# LEDController.net
KiCad netlist of a schematic drawn in Altium Designer
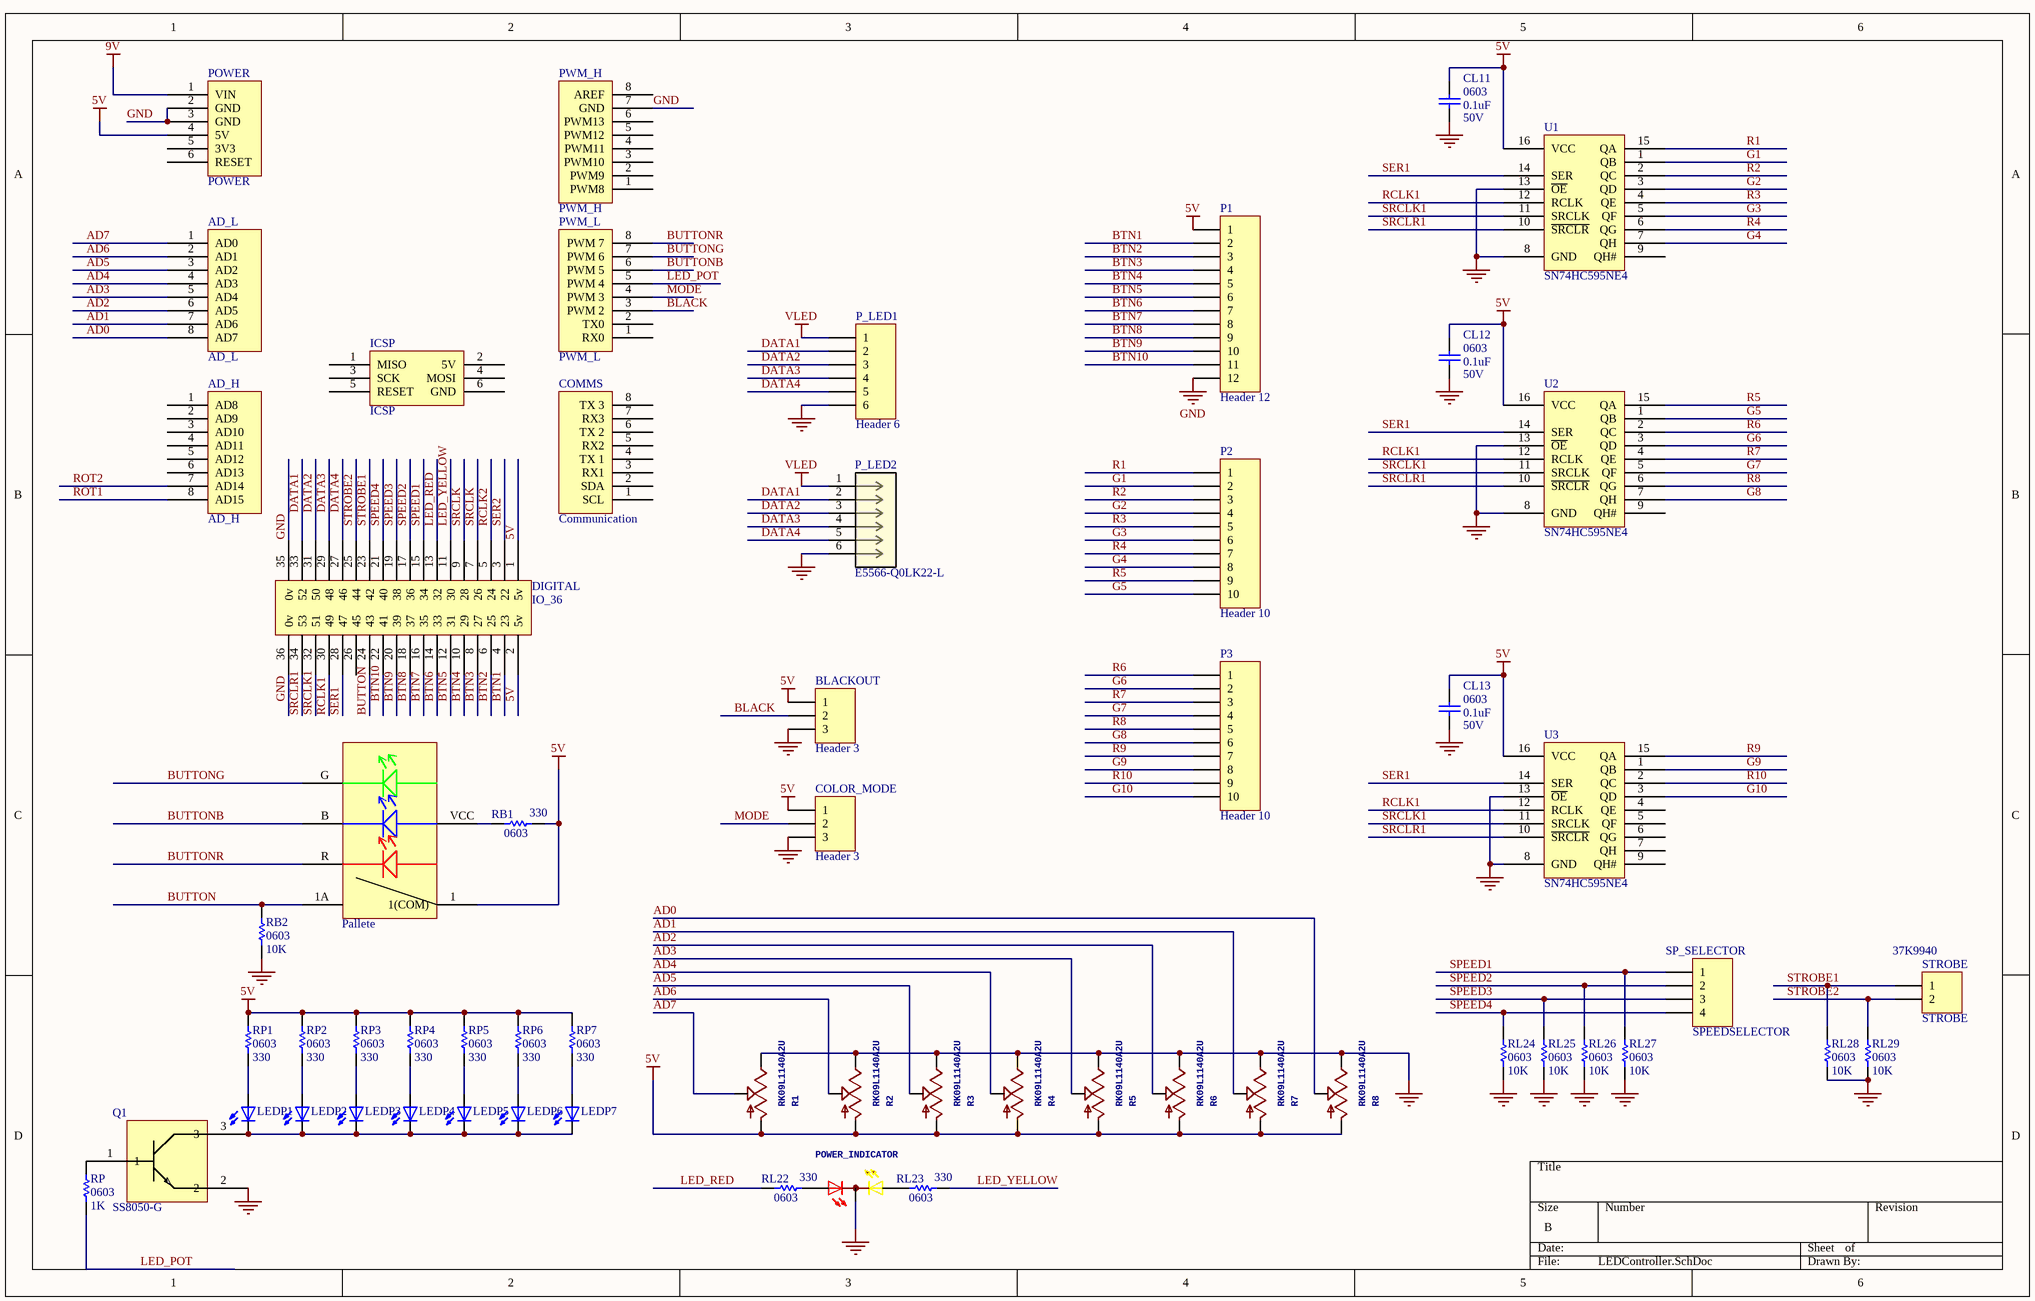
[diagram p0: LEDController.SchDoc]

(export (version "E")
  (design (tool "Eeschema 10.0.6"))
  (components
    (comp (ref "AD_H")
      (value "AD_H")
      (footprint "Header 8x1 8.5mm")
      (description "CONN HEADER VERT 8POS 2.54MM")
      (libsource (lib "Schlib") (part "AD_H"))
    )
    (comp (ref "AD_L")
      (value "AD_L")
      (footprint "Header 8x1 8.5mm")
      (description "CONN HEADER VERT 8POS 2.54MM")
      (libsource (lib "Schlib") (part "AD_L"))
    )
    (comp (ref "BLACKOUT")
      (value "Header 3")
      (footprint "B3B-PH-K-S(LF)(SN)")
      (description "CONN HEADER VERT 3POS 2MM")
      (fields (field (name "PUBLISHER") "Altium Limited"))
      (libsource (lib "Miscellaneous Connectors") (part "Header 3"))
    )
    (comp (ref "CL11")
      (value "0603")
      (footprint "C0603")
      (description "CAP CER 0.1UF 50V X5R 0603")
      (fields
        (field (name "ALTIUM_VALUE") "0.1uF")
        (field (name "VOLTAGE RATING") "50V")
        (field (name "TOLERANCE") "10%")
      )
      (libsource (lib "Miscellaneous Devices") (part "Cap"))
    )
    (comp (ref "CL12")
      (value "0603")
      (footprint "C0603")
      (description "CAP CER 0.1UF 50V X5R 0603")
      (fields
        (field (name "ALTIUM_VALUE") "0.1uF")
        (field (name "VOLTAGE RATING") "50V")
        (field (name "TOLERANCE") "10%")
      )
      (libsource (lib "Miscellaneous Devices") (part "Cap"))
    )
    (comp (ref "CL13")
      (value "0603")
      (footprint "C0603")
      (description "CAP CER 0.1UF 50V X5R 0603")
      (fields
        (field (name "ALTIUM_VALUE") "0.1uF")
        (field (name "VOLTAGE RATING") "50V")
        (field (name "TOLERANCE") "10%")
      )
      (libsource (lib "Miscellaneous Devices") (part "Cap"))
    )
    (comp (ref "COLOR_MODE")
      (value "Header 3")
      (footprint "B3B-PH-K-S(LF)(SN)")
      (description "CONN HEADER VERT 3POS 2MM")
      (fields (field (name "PUBLISHER") "Altium Limited"))
      (libsource (lib "Miscellaneous Connectors") (part "Header 3"))
    )
    (comp (ref "COMMS")
      (value "Communication")
      (footprint "Header 8x1 8.5mm")
      (description "CONN HEADER VERT 8POS 2.54MM")
      (libsource (lib "Schlib") (part "Communication"))
    )
    (comp (ref "DIGITAL")
      (value "IO_36")
      (footprint "HEADER 36X 8MM")
      (description "CONN HEADER VERT 36POS 2.54MM")
      (libsource (lib "Schlib") (part "IO_36"))
    )
    (comp (ref "ICSP") (value "ICSP") (footprint "ICSP") (libsource (lib "Schlib") (part "ICSP")))
    (comp (ref "LEDP1")
      (value "150060AS75000")
      (footprint "LED-0603-Amber")
      (description "Amber 605nm LED Indication - Discrete 2V 0603 (1608 Metric)")
      (libsource (lib "Schlib") (part "150060AS75000"))
    )
    (comp (ref "LEDP2")
      (value "150060AS75000")
      (footprint "LED-0603-Amber")
      (description "Amber 605nm LED Indication - Discrete 2V 0603 (1608 Metric)")
      (libsource (lib "Schlib") (part "150060AS75000"))
    )
    (comp (ref "LEDP3")
      (value "150060AS75000")
      (footprint "LED-0603-Amber")
      (description "Amber 605nm LED Indication - Discrete 2V 0603 (1608 Metric)")
      (libsource (lib "Schlib") (part "150060AS75000"))
    )
    (comp (ref "LEDP4")
      (value "150060AS75000")
      (footprint "LED-0603-Amber")
      (description "Amber 605nm LED Indication - Discrete 2V 0603 (1608 Metric)")
      (libsource (lib "Schlib") (part "150060AS75000"))
    )
    (comp (ref "LEDP5")
      (value "150060AS75000")
      (footprint "LED-0603-Amber")
      (description "Amber 605nm LED Indication - Discrete 2V 0603 (1608 Metric)")
      (libsource (lib "Schlib") (part "150060AS75000"))
    )
    (comp (ref "LEDP6")
      (value "150060AS75000")
      (footprint "LED-0603-Amber")
      (description "Amber 605nm LED Indication - Discrete 2V 0603 (1608 Metric)")
      (libsource (lib "Schlib") (part "150060AS75000"))
    )
    (comp (ref "LEDP7")
      (value "150060AS75000")
      (footprint "LED-0603-Amber")
      (description "Amber 605nm LED Indication - Discrete 2V 0603 (1608 Metric)")
      (libsource (lib "Schlib") (part "150060AS75000"))
    )
    (comp (ref "P1")
      (value "Header 12")
      (footprint "12Pos Header")
      (description "CONN HEADER VERT 12POS 2.54MM")
      (libsource (lib "Miscellaneous Connectors") (part "Header 12"))
    )
    (comp (ref "P2")
      (value "Header 10")
      (footprint "10POS HEADER")
      (description "CONN HEADER VERT 10POS 2.54MM")
      (fields (field (name "PUBLISHER") "Altium Limited"))
      (libsource (lib "Miscellaneous Connectors") (part "Header 10"))
    )
    (comp (ref "P3")
      (value "Header 10")
      (footprint "10POS HEADER")
      (description "CONN HEADER VERT 10POS 2.54MM")
      (fields (field (name "PUBLISHER") "Altium Limited"))
      (libsource (lib "Miscellaneous Connectors") (part "Header 10"))
    )
    (comp (ref "Pallete")
      (value "KP0115ANBKG03RGB-2SJB")
      (footprint "KP0115ANBKG03RGB-2SJB")
      (description "Pushbutton Switch SPST-NO Standard, Illuminated Through Hole")
      (libsource (lib "Schlib") (part "KP0115ANBKG03RGB-2SJB"))
    )
    (comp (ref "POWER")
      (value "POWER")
      (footprint "Header 6x1 8.5mm")
      (description "CONN HEADER VERT 6POS 2.54MM")
      (libsource (lib "Schlib") (part "POWER"))
    )
    (comp (ref "POWER_INDICATOR")
      (value "WP59EYW")
      (footprint "DUOLED-C-5MM")
      (description "Red, Yellow 617nm Red, 588nm Yellow LED Indication - Discrete 2V Red, 2.1V Yellow Radial - 3 Leads")
      (libsource (lib "Schlib") (part "WP59EYW"))
    )
    (comp (ref "PWM_H")
      (value "PWM_H")
      (footprint "Header 8x1 8.5mm")
      (description "CONN HEADER VERT 8POS 2.54MM")
      (libsource (lib "Schlib") (part "PWM_H"))
    )
    (comp (ref "PWM_L")
      (value "PWM_L")
      (footprint "Header 8x1 8.5mm")
      (description "CONN HEADER VERT 8POS 2.54MM")
      (libsource (lib "Schlib") (part "PWM_L"))
    )
    (comp (ref "P_LED1")
      (value "Header 6")
      (footprint "HDR1X6")
      (description "CONN HEADER VERT 6POS 2.54MM")
      (fields (field (name "PUBLISHER") "Altium Limited"))
      (libsource (lib "Miscellaneous Connectors") (part "Header 6"))
    )
    (comp (ref "P_LED2")
      (value "E5566-Q0LK22-L")
      (footprint "E5566Q0LK22L")
      (description "CONN MOD JACK 6P6C R/A UNSHLD")
      (fields (field (name "COPYRIGHT") "Copyright (C) 2016 Accelerated Designs. All rights reserved"))
      (libsource (lib "Schlib") (part "E5566-Q0LK22-L"))
    )
    (comp (ref "Q1")
      (value "SS8050-G")
      (footprint "TRAN_SS8050-G_CIP")
      (description "Bipolar (BJT) Transistor NPN 25V 1.5A 100MHz 300mW Surface Mount SOT-23")
      (fields (field (name "COPYRIGHT") "Copyright (C) 2018 Accelerated Designs. All rights reserved"))
      (libsource (lib "Schlib") (part "SS8050-G"))
    )
    (comp (ref "R1")
      (value "RK09L1140A2U")
      (footprint "EVUFXM")
      (description "Potentiometers Sgl Unit Vert Flat Snap-in 10K Ohms 20%")
      (fields (field (name "TOLERANCE") "20%"))
      (libsource (lib "Schlib") (part "US-EVUM"))
    )
    (comp (ref "R2")
      (value "RK09L1140A2U")
      (footprint "EVUFXM")
      (description "Potentiometers Sgl Unit Vert Flat Snap-in 10K Ohms 20%")
      (fields (field (name "TOLERANCE") "20%"))
      (libsource (lib "Schlib") (part "US-EVUM"))
    )
    (comp (ref "R3")
      (value "RK09L1140A2U")
      (footprint "EVUFXM")
      (description "Potentiometers Sgl Unit Vert Flat Snap-in 10K Ohms 20%")
      (fields (field (name "TOLERANCE") "20%"))
      (libsource (lib "Schlib") (part "US-EVUM"))
    )
    (comp (ref "R4")
      (value "RK09L1140A2U")
      (footprint "EVUFXM")
      (description "Potentiometers Sgl Unit Vert Flat Snap-in 10K Ohms 20%")
      (fields (field (name "TOLERANCE") "20%"))
      (libsource (lib "Schlib") (part "US-EVUM"))
    )
    (comp (ref "R5")
      (value "RK09L1140A2U")
      (footprint "EVUFXM")
      (description "Potentiometers Sgl Unit Vert Flat Snap-in 10K Ohms 20%")
      (fields (field (name "TOLERANCE") "20%"))
      (libsource (lib "Schlib") (part "US-EVUM"))
    )
    (comp (ref "R6")
      (value "RK09L1140A2U")
      (footprint "EVUFXM")
      (description "Potentiometers Sgl Unit Vert Flat Snap-in 10K Ohms 20%")
      (fields (field (name "TOLERANCE") "20%"))
      (libsource (lib "Schlib") (part "US-EVUM"))
    )
    (comp (ref "R7")
      (value "RK09L1140A2U")
      (footprint "EVUFXM")
      (description "Potentiometers Sgl Unit Vert Flat Snap-in 10K Ohms 20%")
      (fields (field (name "TOLERANCE") "20%"))
      (libsource (lib "Schlib") (part "US-EVUM"))
    )
    (comp (ref "R8")
      (value "RK09L1140A2U")
      (footprint "EVUFXM")
      (description "Potentiometers Sgl Unit Vert Flat Snap-in 10K Ohms 20%")
      (fields (field (name "TOLERANCE") "20%"))
      (libsource (lib "Schlib") (part "US-EVUM"))
    )
    (comp (ref "RB1")
      (value "0603")
      (footprint "R0603")
      (description "RES SMD 330 OHM 1% 1/10W 0603")
      (fields (field (name "ALTIUM_VALUE") "330") (field (name "TOLERANCE") "1%"))
      (libsource (lib "Miscellaneous Devices") (part "Res1"))
    )
    (comp (ref "RB2")
      (value "0603")
      (footprint "R0603")
      (description "RES SMD 10K OHM 5% 1/10W 0603")
      (fields (field (name "ALTIUM_VALUE") "10K") (field (name "TOLERANCE") "5%"))
      (libsource (lib "Miscellaneous Devices") (part "Res1"))
    )
    (comp (ref "RL22")
      (value "0603")
      (footprint "R0603")
      (description "RES SMD 330 OHM 1% 1/10W 0603")
      (fields (field (name "ALTIUM_VALUE") "330") (field (name "TOLERANCE") "1%"))
      (libsource (lib "Miscellaneous Devices") (part "Res1"))
    )
    (comp (ref "RL23")
      (value "0603")
      (footprint "R0603")
      (description "RES SMD 330 OHM 1% 1/10W 0603")
      (fields (field (name "ALTIUM_VALUE") "330") (field (name "TOLERANCE") "1%"))
      (libsource (lib "Miscellaneous Devices") (part "Res1"))
    )
    (comp (ref "RL24")
      (value "0603")
      (footprint "R0603")
      (description "RES SMD 10K OHM 5% 1/10W 0603")
      (fields (field (name "ALTIUM_VALUE") "10K") (field (name "TOLERANCE") "5%"))
      (libsource (lib "Miscellaneous Devices") (part "Res1"))
    )
    (comp (ref "RL25")
      (value "0603")
      (footprint "R0603")
      (description "RES SMD 10K OHM 5% 1/10W 0603")
      (fields (field (name "ALTIUM_VALUE") "10K") (field (name "TOLERANCE") "5%"))
      (libsource (lib "Miscellaneous Devices") (part "Res1"))
    )
    (comp (ref "RL26")
      (value "0603")
      (footprint "R0603")
      (description "RES SMD 10K OHM 5% 1/10W 0603")
      (fields (field (name "ALTIUM_VALUE") "10K") (field (name "TOLERANCE") "5%"))
      (libsource (lib "Miscellaneous Devices") (part "Res1"))
    )
    (comp (ref "RL27")
      (value "0603")
      (footprint "R0603")
      (description "RES SMD 10K OHM 5% 1/10W 0603")
      (fields (field (name "ALTIUM_VALUE") "10K") (field (name "TOLERANCE") "5%"))
      (libsource (lib "Miscellaneous Devices") (part "Res1"))
    )
    (comp (ref "RL28")
      (value "0603")
      (footprint "R0603")
      (description "RES SMD 10K OHM 5% 1/10W 0603")
      (fields (field (name "ALTIUM_VALUE") "10K") (field (name "TOLERANCE") "5%"))
      (libsource (lib "Miscellaneous Devices") (part "Res1"))
    )
    (comp (ref "RL29")
      (value "0603")
      (footprint "R0603")
      (description "RES SMD 10K OHM 5% 1/10W 0603")
      (fields (field (name "ALTIUM_VALUE") "10K") (field (name "TOLERANCE") "5%"))
      (libsource (lib "Miscellaneous Devices") (part "Res1"))
    )
    (comp (ref "RP")
      (value "0603")
      (footprint "R0603")
      (description "RES SMD 1K OHM 1% 1/10W 0603")
      (fields
        (field (name "ALTIUM_VALUE") "1K")
        (field (name "MANUFACTURER") "Yageo")
        (field (name "MANUFACTURER PART NUMBER") "RC0603FR-071KL")
      )
      (libsource (lib "Miscellaneous Devices") (part "Res1"))
    )
    (comp (ref "RP1")
      (value "0603")
      (footprint "R0603")
      (description "RES SMD 330 OHM 1% 1/10W 0603")
      (fields (field (name "ALTIUM_VALUE") "330") (field (name "TOLERANCE") "1%"))
      (libsource (lib "Miscellaneous Devices") (part "Res1"))
    )
    (comp (ref "RP2")
      (value "0603")
      (footprint "R0603")
      (description "RES SMD 330 OHM 1% 1/10W 0603")
      (fields (field (name "ALTIUM_VALUE") "330") (field (name "TOLERANCE") "1%"))
      (libsource (lib "Miscellaneous Devices") (part "Res1"))
    )
    (comp (ref "RP3")
      (value "0603")
      (footprint "R0603")
      (description "RES SMD 330 OHM 1% 1/10W 0603")
      (fields (field (name "ALTIUM_VALUE") "330") (field (name "TOLERANCE") "1%"))
      (libsource (lib "Miscellaneous Devices") (part "Res1"))
    )
    (comp (ref "RP4")
      (value "0603")
      (footprint "R0603")
      (description "RES SMD 330 OHM 1% 1/10W 0603")
      (fields (field (name "ALTIUM_VALUE") "330") (field (name "TOLERANCE") "1%"))
      (libsource (lib "Miscellaneous Devices") (part "Res1"))
    )
    (comp (ref "RP5")
      (value "0603")
      (footprint "R0603")
      (description "RES SMD 330 OHM 1% 1/10W 0603")
      (fields (field (name "ALTIUM_VALUE") "330") (field (name "TOLERANCE") "1%"))
      (libsource (lib "Miscellaneous Devices") (part "Res1"))
    )
    (comp (ref "RP6")
      (value "0603")
      (footprint "R0603")
      (description "RES SMD 330 OHM 1% 1/10W 0603")
      (fields (field (name "ALTIUM_VALUE") "330") (field (name "TOLERANCE") "1%"))
      (libsource (lib "Miscellaneous Devices") (part "Res1"))
    )
    (comp (ref "RP7")
      (value "0603")
      (footprint "R0603")
      (description "RES SMD 330 OHM 1% 1/10W 0603")
      (fields (field (name "ALTIUM_VALUE") "330") (field (name "TOLERANCE") "1%"))
      (libsource (lib "Miscellaneous Devices") (part "Res1"))
    )
    (comp (ref "SP_SELECTOR")
      (value "SPEEDSELECTOR")
      (footprint "HDR1X4")
      (description "CONN HEADER VERT 4POS 2.54MM")
      (fields (field (name "PUBLISHER") "Altium Limited"))
      (libsource (lib "Miscellaneous Connectors") (part "Header 4"))
    )
    (comp (ref "STROBE")
      (value "STROBE")
      (footprint "JST_B2B-PH-K-S(LF)(SN)")
      (description "Connector Header Through Hole 2 position 0.079\" (2.00mm)")
      (fields (field (name "SUPPLIER PART NUMBER 1") "37K9940"))
      (libsource (lib "Miscellaneous Connectors") (part "Header 2"))
    )
    (comp (ref "U1")
      (value "SN74HC595NE4")
      (footprint "DIP794W53P254L1930H508Q16N")
      (description "Counter Shift Registers 8-Bit Shift Register")
      (libsource (lib "Schlib") (part "SN74HC595NE4"))
    )
    (comp (ref "U2")
      (value "SN74HC595NE4")
      (footprint "DIP794W53P254L1930H508Q16N")
      (description "Counter Shift Registers 8-Bit Shift Register")
      (libsource (lib "Schlib") (part "SN74HC595NE4"))
    )
    (comp (ref "U3")
      (value "SN74HC595NE4")
      (footprint "DIP794W53P254L1930H508Q16N")
      (description "Counter Shift Registers 8-Bit Shift Register")
      (libsource (lib "Schlib") (part "SN74HC595NE4"))
    )
  )
  (nets
    (net (code "1") (name "/AD0") (class "Default")
      (node (ref "AD_L") (pin "8") (pinfunction "AD7_8") (pintype "passive"))
      (node (ref "R8") (pin "2") (pinfunction "S_2") (pintype "passive"))
    )
    (net (code "2") (name "/AD1") (class "Default")
      (node (ref "AD_L") (pin "7") (pinfunction "AD6_7") (pintype "passive"))
      (node (ref "R7") (pin "2") (pinfunction "S_2") (pintype "passive"))
    )
    (net (code "3") (name "/AD2") (class "Default")
      (node (ref "AD_L") (pin "6") (pinfunction "AD5_6") (pintype "passive"))
      (node (ref "R6") (pin "2") (pinfunction "S_2") (pintype "passive"))
    )
    (net (code "4") (name "/AD3") (class "Default")
      (node (ref "AD_L") (pin "5") (pinfunction "AD4_5") (pintype "passive"))
      (node (ref "R5") (pin "2") (pinfunction "S_2") (pintype "passive"))
    )
    (net (code "5") (name "/AD4") (class "Default")
      (node (ref "AD_L") (pin "4") (pinfunction "AD3_4") (pintype "passive"))
      (node (ref "R4") (pin "2") (pinfunction "S_2") (pintype "passive"))
    )
    (net (code "6") (name "/AD5") (class "Default")
      (node (ref "AD_L") (pin "3") (pinfunction "AD2_3") (pintype "passive"))
      (node (ref "R3") (pin "2") (pinfunction "S_2") (pintype "passive"))
    )
    (net (code "7") (name "/AD6") (class "Default")
      (node (ref "AD_L") (pin "2") (pinfunction "AD1_2") (pintype "passive"))
      (node (ref "R2") (pin "2") (pinfunction "S_2") (pintype "passive"))
    )
    (net (code "8") (name "/AD7") (class "Default")
      (node (ref "AD_L") (pin "1") (pinfunction "AD0_1") (pintype "passive"))
      (node (ref "R1") (pin "2") (pinfunction "S_2") (pintype "passive"))
    )
    (net (code "9") (name "/BLACK") (class "Default")
      (node (ref "BLACKOUT") (pin "2") (pinfunction "2_2") (pintype "passive"))
      (node (ref "PWM_L") (pin "3") (pinfunction "PWM_2_3") (pintype "passive"))
    )
    (net (code "10") (name "/BTN1") (class "Default")
      (node (ref "DIGITAL") (pin "4") (pinfunction "23_4") (pintype "passive"))
      (node (ref "P1") (pin "2") (pinfunction "2_2") (pintype "passive"))
    )
    (net (code "11") (name "/BTN2") (class "Default")
      (node (ref "DIGITAL") (pin "6") (pinfunction "25_6") (pintype "passive"))
      (node (ref "P1") (pin "3") (pinfunction "3_3") (pintype "passive"))
    )
    (net (code "12") (name "/BTN3") (class "Default")
      (node (ref "DIGITAL") (pin "8") (pinfunction "27_8") (pintype "passive"))
      (node (ref "P1") (pin "4") (pinfunction "4_4") (pintype "passive"))
    )
    (net (code "13") (name "/BTN4") (class "Default")
      (node (ref "DIGITAL") (pin "10") (pinfunction "29_10") (pintype "passive"))
      (node (ref "P1") (pin "5") (pinfunction "5_5") (pintype "passive"))
    )
    (net (code "14") (name "/BTN5") (class "Default")
      (node (ref "DIGITAL") (pin "12") (pinfunction "31_12") (pintype "passive"))
      (node (ref "P1") (pin "6") (pinfunction "6_6") (pintype "passive"))
    )
    (net (code "15") (name "/BTN6") (class "Default")
      (node (ref "DIGITAL") (pin "14") (pinfunction "33_14") (pintype "passive"))
      (node (ref "P1") (pin "7") (pinfunction "7_7") (pintype "passive"))
    )
    (net (code "16") (name "/BTN7") (class "Default")
      (node (ref "DIGITAL") (pin "16") (pinfunction "35_16") (pintype "passive"))
      (node (ref "P1") (pin "8") (pinfunction "8_8") (pintype "passive"))
    )
    (net (code "17") (name "/BTN8") (class "Default")
      (node (ref "DIGITAL") (pin "18") (pinfunction "37_18") (pintype "passive"))
      (node (ref "P1") (pin "9") (pinfunction "9_9") (pintype "passive"))
    )
    (net (code "18") (name "/BTN9") (class "Default")
      (node (ref "DIGITAL") (pin "20") (pinfunction "39_20") (pintype "passive"))
      (node (ref "P1") (pin "10") (pinfunction "10_10") (pintype "passive"))
    )
    (net (code "19") (name "/BTN10") (class "Default")
      (node (ref "DIGITAL") (pin "22") (pinfunction "41_22") (pintype "passive"))
      (node (ref "P1") (pin "11") (pinfunction "11_11") (pintype "passive"))
    )
    (net (code "20") (name "/BUTTON") (class "Default")
      (node (ref "DIGITAL") (pin "24") (pinfunction "43_24") (pintype "passive"))
      (node (ref "Pallete") (pin "1A") (pinfunction "1A_1A") (pintype "passive"))
      (node (ref "RB2") (pin "1") (pinfunction "1_1") (pintype "passive"))
    )
    (net (code "21") (name "/BUTTONB") (class "Default")
      (node (ref "PWM_L") (pin "6") (pinfunction "PWM_5_6") (pintype "passive"))
      (node (ref "Pallete") (pin "B") (pinfunction "B(-)_B") (pintype "passive"))
    )
    (net (code "22") (name "/BUTTONG") (class "Default")
      (node (ref "PWM_L") (pin "7") (pinfunction "PWM_6_7") (pintype "passive"))
      (node (ref "Pallete") (pin "G") (pinfunction "G(-)_G") (pintype "passive"))
    )
    (net (code "23") (name "/BUTTONR") (class "Default")
      (node (ref "PWM_L") (pin "8") (pinfunction "PWM_7_8") (pintype "passive"))
      (node (ref "Pallete") (pin "R") (pinfunction "R(-)_R") (pintype "passive"))
    )
    (net (code "24") (name "/DATA1") (class "Default")
      (node (ref "DIGITAL") (pin "33") (pinfunction "52_33") (pintype "passive"))
      (node (ref "P_LED1") (pin "2") (pinfunction "2_2") (pintype "passive"))
      (node (ref "P_LED2") (pin "2") (pinfunction "2_2") (pintype "passive"))
    )
    (net (code "25") (name "/DATA2") (class "Default")
      (node (ref "DIGITAL") (pin "31") (pinfunction "50_31") (pintype "passive"))
      (node (ref "P_LED1") (pin "3") (pinfunction "3_3") (pintype "passive"))
      (node (ref "P_LED2") (pin "3") (pinfunction "3_3") (pintype "passive"))
    )
    (net (code "26") (name "/DATA3") (class "Default")
      (node (ref "DIGITAL") (pin "29") (pinfunction "48_29") (pintype "passive"))
      (node (ref "P_LED1") (pin "4") (pinfunction "4_4") (pintype "passive"))
      (node (ref "P_LED2") (pin "4") (pinfunction "4_4") (pintype "passive"))
    )
    (net (code "27") (name "/DATA4") (class "Default")
      (node (ref "DIGITAL") (pin "27") (pinfunction "46_27") (pintype "passive"))
      (node (ref "P_LED1") (pin "5") (pinfunction "5_5") (pintype "passive"))
      (node (ref "P_LED2") (pin "5") (pinfunction "5_5") (pintype "passive"))
    )
    (net (code "28") (name "/G1") (class "Default")
      (node (ref "P2") (pin "2") (pinfunction "2_2") (pintype "passive"))
      (node (ref "U1") (pin "1") (pinfunction "QB_1") (pintype "passive"))
    )
    (net (code "29") (name "/G2") (class "Default")
      (node (ref "P2") (pin "4") (pinfunction "4_4") (pintype "passive"))
      (node (ref "U1") (pin "3") (pinfunction "QD_3") (pintype "passive"))
    )
    (net (code "30") (name "/G3") (class "Default")
      (node (ref "P2") (pin "6") (pinfunction "6_6") (pintype "passive"))
      (node (ref "U1") (pin "5") (pinfunction "QF_5") (pintype "passive"))
    )
    (net (code "31") (name "/G4") (class "Default")
      (node (ref "P2") (pin "8") (pinfunction "8_8") (pintype "passive"))
      (node (ref "U1") (pin "7") (pinfunction "QH_7") (pintype "passive"))
    )
    (net (code "32") (name "/G5") (class "Default")
      (node (ref "P2") (pin "10") (pinfunction "10_10") (pintype "passive"))
      (node (ref "U2") (pin "1") (pinfunction "QB_1") (pintype "passive"))
    )
    (net (code "33") (name "/G6") (class "Default")
      (node (ref "P3") (pin "2") (pinfunction "2_2") (pintype "passive"))
      (node (ref "U2") (pin "3") (pinfunction "QD_3") (pintype "passive"))
    )
    (net (code "34") (name "/G7") (class "Default")
      (node (ref "P3") (pin "4") (pinfunction "4_4") (pintype "passive"))
      (node (ref "U2") (pin "5") (pinfunction "QF_5") (pintype "passive"))
    )
    (net (code "35") (name "/G8") (class "Default")
      (node (ref "P3") (pin "6") (pinfunction "6_6") (pintype "passive"))
      (node (ref "U2") (pin "7") (pinfunction "QH_7") (pintype "passive"))
    )
    (net (code "36") (name "/G9") (class "Default")
      (node (ref "P3") (pin "8") (pinfunction "8_8") (pintype "passive"))
      (node (ref "U3") (pin "1") (pinfunction "QB_1") (pintype "passive"))
    )
    (net (code "37") (name "/G10") (class "Default")
      (node (ref "P3") (pin "10") (pinfunction "10_10") (pintype "passive"))
      (node (ref "U3") (pin "3") (pinfunction "QD_3") (pintype "passive"))
    )
    (net (code "38") (name "/LED_POT") (class "Default")
      (node (ref "PWM_L") (pin "5") (pinfunction "PWM_4_5") (pintype "passive"))
      (node (ref "RP") (pin "2") (pinfunction "2_2") (pintype "passive"))
    )
    (net (code "39") (name "/LED_RED") (class "Default")
      (node (ref "DIGITAL") (pin "13") (pinfunction "32_13") (pintype "passive"))
      (node (ref "RL22") (pin "1") (pinfunction "1_1") (pintype "passive"))
    )
    (net (code "40") (name "/LED_YELLOW") (class "Default")
      (node (ref "DIGITAL") (pin "11") (pinfunction "30_11") (pintype "passive"))
      (node (ref "RL23") (pin "2") (pinfunction "2_2") (pintype "passive"))
    )
    (net (code "41") (name "/MODE") (class "Default")
      (node (ref "COLOR_MODE") (pin "2") (pinfunction "2_2") (pintype "passive"))
      (node (ref "PWM_L") (pin "4") (pinfunction "PWM_3_4") (pintype "passive"))
    )
    (net (code "42") (name "/R1") (class "Default")
      (node (ref "P2") (pin "1") (pinfunction "1_1") (pintype "passive"))
      (node (ref "U1") (pin "15") (pinfunction "QA_15") (pintype "passive"))
    )
    (net (code "43") (name "/R2") (class "Default")
      (node (ref "P2") (pin "3") (pinfunction "3_3") (pintype "passive"))
      (node (ref "U1") (pin "2") (pinfunction "QC_2") (pintype "passive"))
    )
    (net (code "44") (name "/R3") (class "Default")
      (node (ref "P2") (pin "5") (pinfunction "5_5") (pintype "passive"))
      (node (ref "U1") (pin "4") (pinfunction "QE_4") (pintype "passive"))
    )
    (net (code "45") (name "/R4") (class "Default")
      (node (ref "P2") (pin "7") (pinfunction "7_7") (pintype "passive"))
      (node (ref "U1") (pin "6") (pinfunction "QG_6") (pintype "passive"))
    )
    (net (code "46") (name "/R5") (class "Default")
      (node (ref "P2") (pin "9") (pinfunction "9_9") (pintype "passive"))
      (node (ref "U2") (pin "15") (pinfunction "QA_15") (pintype "passive"))
    )
    (net (code "47") (name "/R6") (class "Default")
      (node (ref "P3") (pin "1") (pinfunction "1_1") (pintype "passive"))
      (node (ref "U2") (pin "2") (pinfunction "QC_2") (pintype "passive"))
    )
    (net (code "48") (name "/R7") (class "Default")
      (node (ref "P3") (pin "3") (pinfunction "3_3") (pintype "passive"))
      (node (ref "U2") (pin "4") (pinfunction "QE_4") (pintype "passive"))
    )
    (net (code "49") (name "/R8") (class "Default")
      (node (ref "P3") (pin "5") (pinfunction "5_5") (pintype "passive"))
      (node (ref "U2") (pin "6") (pinfunction "QG_6") (pintype "passive"))
    )
    (net (code "50") (name "/R9") (class "Default")
      (node (ref "P3") (pin "7") (pinfunction "7_7") (pintype "passive"))
      (node (ref "U3") (pin "15") (pinfunction "QA_15") (pintype "passive"))
    )
    (net (code "51") (name "/R10") (class "Default")
      (node (ref "P3") (pin "9") (pinfunction "9_9") (pintype "passive"))
      (node (ref "U3") (pin "2") (pinfunction "QC_2") (pintype "passive"))
    )
    (net (code "52") (name "/RCLK1") (class "Default")
      (node (ref "DIGITAL") (pin "30") (pinfunction "49_30") (pintype "passive"))
      (node (ref "U1") (pin "12") (pinfunction "RCLK_12") (pintype "passive"))
      (node (ref "U2") (pin "12") (pinfunction "RCLK_12") (pintype "passive"))
      (node (ref "U3") (pin "12") (pinfunction "RCLK_12") (pintype "passive"))
    )
    (net (code "53") (name "/RCLK2") (class "Default")
      (node (ref "DIGITAL") (pin "5") (pinfunction "24_5") (pintype "passive"))
    )
    (net (code "54") (name "/ROT1") (class "Default")
      (node (ref "AD_H") (pin "8") (pinfunction "AD15_8") (pintype "passive"))
    )
    (net (code "55") (name "/ROT2") (class "Default")
      (node (ref "AD_H") (pin "7") (pinfunction "AD14_7") (pintype "passive"))
    )
    (net (code "56") (name "/SER1") (class "Default")
      (node (ref "DIGITAL") (pin "28") (pinfunction "47_28") (pintype "passive"))
      (node (ref "U1") (pin "14") (pinfunction "SER_14") (pintype "passive"))
      (node (ref "U2") (pin "14") (pinfunction "SER_14") (pintype "passive"))
      (node (ref "U3") (pin "14") (pinfunction "SER_14") (pintype "passive"))
    )
    (net (code "57") (name "/SER2") (class "Default")
      (node (ref "DIGITAL") (pin "3") (pinfunction "22_3") (pintype "passive"))
    )
    (net (code "58") (name "/SPEED1") (class "Default")
      (node (ref "DIGITAL") (pin "15") (pinfunction "34_15") (pintype "passive"))
      (node (ref "RL27") (pin "1") (pinfunction "1_1") (pintype "passive"))
      (node (ref "SP_SELECTOR") (pin "1") (pinfunction "1_1") (pintype "passive"))
    )
    (net (code "59") (name "/SPEED2") (class "Default")
      (node (ref "DIGITAL") (pin "17") (pinfunction "36_17") (pintype "passive"))
      (node (ref "RL26") (pin "1") (pinfunction "1_1") (pintype "passive"))
      (node (ref "SP_SELECTOR") (pin "2") (pinfunction "2_2") (pintype "passive"))
    )
    (net (code "60") (name "/SPEED3") (class "Default")
      (node (ref "DIGITAL") (pin "19") (pinfunction "38_19") (pintype "passive"))
      (node (ref "RL25") (pin "1") (pinfunction "1_1") (pintype "passive"))
      (node (ref "SP_SELECTOR") (pin "3") (pinfunction "3_3") (pintype "passive"))
    )
    (net (code "61") (name "/SPEED4") (class "Default")
      (node (ref "DIGITAL") (pin "21") (pinfunction "40_21") (pintype "passive"))
      (node (ref "RL24") (pin "1") (pinfunction "1_1") (pintype "passive"))
      (node (ref "SP_SELECTOR") (pin "4") (pinfunction "4_4") (pintype "passive"))
    )
    (net (code "62") (name "/SRCLK") (class "Default")
      (node (ref "DIGITAL") (pin "7") (pinfunction "26_7") (pintype "passive"))
    )
    (net (code "63") (name "/SRCLK1") (class "Default")
      (node (ref "DIGITAL") (pin "32") (pinfunction "51_32") (pintype "passive"))
      (node (ref "U1") (pin "11") (pinfunction "SRCLK_11") (pintype "passive"))
      (node (ref "U2") (pin "11") (pinfunction "SRCLK_11") (pintype "passive"))
      (node (ref "U3") (pin "11") (pinfunction "SRCLK_11") (pintype "passive"))
    )
    (net (code "64") (name "/STROBE1") (class "Default")
      (node (ref "DIGITAL") (pin "23") (pinfunction "42_23") (pintype "passive"))
      (node (ref "RL28") (pin "1") (pinfunction "1_1") (pintype "passive"))
      (node (ref "STROBE") (pin "1") (pinfunction "1_1") (pintype "passive"))
    )
    (net (code "65") (name "/STROBE2") (class "Default")
      (node (ref "DIGITAL") (pin "25") (pinfunction "44_25") (pintype "passive"))
      (node (ref "RL29") (pin "1") (pinfunction "1_1") (pintype "passive"))
      (node (ref "STROBE") (pin "2") (pinfunction "2_2") (pintype "passive"))
    )
    (net (code "66") (name "/~{SRCLK}") (class "Default")
      (node (ref "DIGITAL") (pin "9") (pinfunction "28_9") (pintype "passive"))
    )
    (net (code "67") (name "/~{SRCLR}1") (class "Default")
      (node (ref "DIGITAL") (pin "34") (pinfunction "53_34") (pintype "passive"))
      (node (ref "U1") (pin "10") (pinfunction "~{SRCLR}_10") (pintype "passive"))
      (node (ref "U2") (pin "10") (pinfunction "~{SRCLR}_10") (pintype "passive"))
      (node (ref "U3") (pin "10") (pinfunction "~{SRCLR}_10") (pintype "passive"))
    )
    (net (code "68") (name "5V") (class "Default")
      (node (ref "BLACKOUT") (pin "1") (pinfunction "1_1") (pintype "passive"))
      (node (ref "CL11") (pin "2") (pinfunction "2_2") (pintype "passive"))
      (node (ref "CL12") (pin "2") (pinfunction "2_2") (pintype "passive"))
      (node (ref "CL13") (pin "2") (pinfunction "2_2") (pintype "passive"))
      (node (ref "COLOR_MODE") (pin "1") (pinfunction "1_1") (pintype "passive"))
      (node (ref "DIGITAL") (pin "1") (pinfunction "5v_1") (pintype "passive"))
      (node (ref "DIGITAL") (pin "2") (pinfunction "5v_2") (pintype "passive"))
      (node (ref "P1") (pin "1") (pinfunction "1_1") (pintype "passive"))
      (node (ref "POWER") (pin "4") (pinfunction "5V_4") (pintype "power_in"))
      (node (ref "Pallete") (pin "1") (pinfunction "1(COM)_1") (pintype "passive"))
      (node (ref "R1") (pin "1") (pinfunction "A_1") (pintype "passive"))
      (node (ref "R2") (pin "1") (pinfunction "A_1") (pintype "passive"))
      (node (ref "R3") (pin "1") (pinfunction "A_1") (pintype "passive"))
      (node (ref "R4") (pin "1") (pinfunction "A_1") (pintype "passive"))
      (node (ref "R5") (pin "1") (pinfunction "A_1") (pintype "passive"))
      (node (ref "R6") (pin "1") (pinfunction "A_1") (pintype "passive"))
      (node (ref "R7") (pin "1") (pinfunction "A_1") (pintype "passive"))
      (node (ref "R8") (pin "1") (pinfunction "A_1") (pintype "passive"))
      (node (ref "RB1") (pin "2") (pinfunction "2_2") (pintype "passive"))
      (node (ref "RP1") (pin "2") (pinfunction "2_2") (pintype "passive"))
      (node (ref "RP2") (pin "2") (pinfunction "2_2") (pintype "passive"))
      (node (ref "RP3") (pin "2") (pinfunction "2_2") (pintype "passive"))
      (node (ref "RP4") (pin "2") (pinfunction "2_2") (pintype "passive"))
      (node (ref "RP5") (pin "2") (pinfunction "2_2") (pintype "passive"))
      (node (ref "RP6") (pin "2") (pinfunction "2_2") (pintype "passive"))
      (node (ref "RP7") (pin "2") (pinfunction "2_2") (pintype "passive"))
      (node (ref "U1") (pin "16") (pinfunction "VCC_16") (pintype "passive"))
      (node (ref "U2") (pin "16") (pinfunction "VCC_16") (pintype "passive"))
      (node (ref "U3") (pin "16") (pinfunction "VCC_16") (pintype "passive"))
    )
    (net (code "69") (name "9V") (class "Default")
      (node (ref "POWER") (pin "1") (pinfunction "VIN_1") (pintype "power_in"))
    )
    (net (code "70") (name "GND") (class "Default")
      (node (ref "BLACKOUT") (pin "3") (pinfunction "3_3") (pintype "passive"))
      (node (ref "CL11") (pin "1") (pinfunction "1_1") (pintype "passive"))
      (node (ref "CL12") (pin "1") (pinfunction "1_1") (pintype "passive"))
      (node (ref "CL13") (pin "1") (pinfunction "1_1") (pintype "passive"))
      (node (ref "COLOR_MODE") (pin "3") (pinfunction "3_3") (pintype "passive"))
      (node (ref "DIGITAL") (pin "35") (pinfunction "0v_35") (pintype "passive"))
      (node (ref "DIGITAL") (pin "36") (pinfunction "0v_36") (pintype "passive"))
      (node (ref "P1") (pin "12") (pinfunction "12_12") (pintype "passive"))
      (node (ref "POWER") (pin "2") (pinfunction "GND_2") (pintype "power_in"))
      (node (ref "POWER") (pin "3") (pinfunction "GND_3") (pintype "power_in"))
      (node (ref "POWER_INDICATOR") (pin "2") (pinfunction "2_2") (pintype "passive"))
      (node (ref "PWM_H") (pin "7") (pinfunction "GND_7") (pintype "passive"))
      (node (ref "P_LED1") (pin "6") (pinfunction "6_6") (pintype "passive"))
      (node (ref "P_LED2") (pin "6") (pinfunction "6_6") (pintype "passive"))
      (node (ref "Q1") (pin "2") (pinfunction "2_2") (pintype "passive"))
      (node (ref "R1") (pin "3") (pinfunction "E_3") (pintype "passive"))
      (node (ref "R2") (pin "3") (pinfunction "E_3") (pintype "passive"))
      (node (ref "R3") (pin "3") (pinfunction "E_3") (pintype "passive"))
      (node (ref "R4") (pin "3") (pinfunction "E_3") (pintype "passive"))
      (node (ref "R5") (pin "3") (pinfunction "E_3") (pintype "passive"))
      (node (ref "R6") (pin "3") (pinfunction "E_3") (pintype "passive"))
      (node (ref "R7") (pin "3") (pinfunction "E_3") (pintype "passive"))
      (node (ref "R8") (pin "3") (pinfunction "E_3") (pintype "passive"))
      (node (ref "RB2") (pin "2") (pinfunction "2_2") (pintype "passive"))
      (node (ref "RL24") (pin "2") (pinfunction "2_2") (pintype "passive"))
      (node (ref "RL25") (pin "2") (pinfunction "2_2") (pintype "passive"))
      (node (ref "RL26") (pin "2") (pinfunction "2_2") (pintype "passive"))
      (node (ref "RL27") (pin "2") (pinfunction "2_2") (pintype "passive"))
      (node (ref "RL28") (pin "2") (pinfunction "2_2") (pintype "passive"))
      (node (ref "RL29") (pin "2") (pinfunction "2_2") (pintype "passive"))
      (node (ref "U1") (pin "13") (pinfunction "~{OE}_13") (pintype "passive"))
      (node (ref "U1") (pin "8") (pinfunction "GND_8") (pintype "passive"))
      (node (ref "U2") (pin "13") (pinfunction "~{OE}_13") (pintype "passive"))
      (node (ref "U2") (pin "8") (pinfunction "GND_8") (pintype "passive"))
      (node (ref "U3") (pin "13") (pinfunction "~{OE}_13") (pintype "passive"))
      (node (ref "U3") (pin "8") (pinfunction "GND_8") (pintype "passive"))
    )
    (net (code "71") (name "Net-(LEDP1-PadA)") (class "Default")
      (node (ref "LEDP1") (pin "A") (pinfunction "A_A") (pintype "passive"))
      (node (ref "RP1") (pin "1") (pinfunction "1_1") (pintype "passive"))
    )
    (net (code "72") (name "Net-(LEDP1-PadC)") (class "Default")
      (node (ref "LEDP1") (pin "C") (pinfunction "C_C") (pintype "passive"))
      (node (ref "LEDP2") (pin "C") (pinfunction "C_C") (pintype "passive"))
      (node (ref "LEDP3") (pin "C") (pinfunction "C_C") (pintype "passive"))
      (node (ref "LEDP4") (pin "C") (pinfunction "C_C") (pintype "passive"))
      (node (ref "LEDP5") (pin "C") (pinfunction "C_C") (pintype "passive"))
      (node (ref "LEDP6") (pin "C") (pinfunction "C_C") (pintype "passive"))
      (node (ref "LEDP7") (pin "C") (pinfunction "C_C") (pintype "passive"))
      (node (ref "Q1") (pin "3") (pinfunction "3_3") (pintype "passive"))
    )
    (net (code "73") (name "Net-(LEDP2-PadA)") (class "Default")
      (node (ref "LEDP2") (pin "A") (pinfunction "A_A") (pintype "passive"))
      (node (ref "RP2") (pin "1") (pinfunction "1_1") (pintype "passive"))
    )
    (net (code "74") (name "Net-(LEDP3-PadA)") (class "Default")
      (node (ref "LEDP3") (pin "A") (pinfunction "A_A") (pintype "passive"))
      (node (ref "RP3") (pin "1") (pinfunction "1_1") (pintype "passive"))
    )
    (net (code "75") (name "Net-(LEDP4-PadA)") (class "Default")
      (node (ref "LEDP4") (pin "A") (pinfunction "A_A") (pintype "passive"))
      (node (ref "RP4") (pin "1") (pinfunction "1_1") (pintype "passive"))
    )
    (net (code "76") (name "Net-(LEDP5-PadA)") (class "Default")
      (node (ref "LEDP5") (pin "A") (pinfunction "A_A") (pintype "passive"))
      (node (ref "RP5") (pin "1") (pinfunction "1_1") (pintype "passive"))
    )
    (net (code "77") (name "Net-(LEDP6-PadA)") (class "Default")
      (node (ref "LEDP6") (pin "A") (pinfunction "A_A") (pintype "passive"))
      (node (ref "RP6") (pin "1") (pinfunction "1_1") (pintype "passive"))
    )
    (net (code "78") (name "Net-(LEDP7-PadA)") (class "Default")
      (node (ref "LEDP7") (pin "A") (pinfunction "A_A") (pintype "passive"))
      (node (ref "RP7") (pin "1") (pinfunction "1_1") (pintype "passive"))
    )
    (net (code "79") (name "Net-(POWER_INDICATOR-Pad1)") (class "Default")
      (node (ref "POWER_INDICATOR") (pin "1") (pinfunction "1_1") (pintype "passive"))
      (node (ref "RL22") (pin "2") (pinfunction "2_2") (pintype "passive"))
    )
    (net (code "80") (name "Net-(POWER_INDICATOR-Pad3)") (class "Default")
      (node (ref "POWER_INDICATOR") (pin "3") (pinfunction "3_3") (pintype "passive"))
      (node (ref "RL23") (pin "1") (pinfunction "1_1") (pintype "passive"))
    )
    (net (code "81") (name "Net-(Pallete-3V3)") (class "Default")
      (node (ref "Pallete") (pin "VCC") (pinfunction "3V3_VCC") (pintype "passive"))
      (node (ref "RB1") (pin "1") (pinfunction "1_1") (pintype "passive"))
    )
    (net (code "82") (name "Net-(Q1-Pad1)") (class "Default")
      (node (ref "Q1") (pin "1") (pinfunction "1_1") (pintype "passive"))
      (node (ref "RP") (pin "1") (pinfunction "1_1") (pintype "passive"))
    )
    (net (code "83") (name "VLED") (class "Default")
      (node (ref "P_LED1") (pin "1") (pinfunction "1_1") (pintype "passive"))
      (node (ref "P_LED2") (pin "1") (pinfunction "1_1") (pintype "passive"))
    )
    (net (code "84") (name "unconnected-(AD_H-AD8-Pad1)") (class "Default")
      (node (ref "AD_H") (pin "1") (pinfunction "AD8_1") (pintype "passive"))
    )
    (net (code "85") (name "unconnected-(AD_H-AD9-Pad2)") (class "Default")
      (node (ref "AD_H") (pin "2") (pinfunction "AD9_2") (pintype "passive"))
    )
    (net (code "86") (name "unconnected-(AD_H-AD10-Pad3)") (class "Default")
      (node (ref "AD_H") (pin "3") (pinfunction "AD10_3") (pintype "passive"))
    )
    (net (code "87") (name "unconnected-(AD_H-AD11-Pad4)") (class "Default")
      (node (ref "AD_H") (pin "4") (pinfunction "AD11_4") (pintype "passive"))
    )
    (net (code "88") (name "unconnected-(AD_H-AD12-Pad5)") (class "Default")
      (node (ref "AD_H") (pin "5") (pinfunction "AD12_5") (pintype "passive"))
    )
    (net (code "89") (name "unconnected-(AD_H-AD13-Pad6)") (class "Default")
      (node (ref "AD_H") (pin "6") (pinfunction "AD13_6") (pintype "passive"))
    )
    (net (code "90") (name "unconnected-(COMMS-RX1-Pad3)") (class "Default")
      (node (ref "COMMS") (pin "3") (pinfunction "RX1_3") (pintype "passive"))
    )
    (net (code "91") (name "unconnected-(COMMS-RX2-Pad5)") (class "Default")
      (node (ref "COMMS") (pin "5") (pinfunction "RX2_5") (pintype "passive"))
    )
    (net (code "92") (name "unconnected-(COMMS-RX3-Pad7)") (class "Default")
      (node (ref "COMMS") (pin "7") (pinfunction "RX3_7") (pintype "passive"))
    )
    (net (code "93") (name "unconnected-(COMMS-SCL-Pad1)") (class "Default")
      (node (ref "COMMS") (pin "1") (pinfunction "SCL_1") (pintype "passive"))
    )
    (net (code "94") (name "unconnected-(COMMS-SDA-Pad2)") (class "Default")
      (node (ref "COMMS") (pin "2") (pinfunction "SDA_2") (pintype "passive"))
    )
    (net (code "95") (name "unconnected-(COMMS-TX_1-Pad4)") (class "Default")
      (node (ref "COMMS") (pin "4") (pinfunction "TX_1_4") (pintype "passive"))
    )
    (net (code "96") (name "unconnected-(COMMS-TX_2-Pad6)") (class "Default")
      (node (ref "COMMS") (pin "6") (pinfunction "TX_2_6") (pintype "passive"))
    )
    (net (code "97") (name "unconnected-(COMMS-TX_3-Pad8)") (class "Default")
      (node (ref "COMMS") (pin "8") (pinfunction "TX_3_8") (pintype "passive"))
    )
    (net (code "98") (name "unconnected-(DIGITAL-45-Pad26)") (class "Default")
      (node (ref "DIGITAL") (pin "26") (pinfunction "45_26") (pintype "passive"))
    )
    (net (code "99") (name "unconnected-(ICSP-5V-Pad2)") (class "Default")
      (node (ref "ICSP") (pin "2") (pinfunction "5V_2") (pintype "power_in"))
    )
    (net (code "100") (name "unconnected-(ICSP-GND-Pad6)") (class "Default")
      (node (ref "ICSP") (pin "6") (pinfunction "GND_6") (pintype "power_in"))
    )
    (net (code "101") (name "unconnected-(ICSP-MISO-Pad1)") (class "Default")
      (node (ref "ICSP") (pin "1") (pinfunction "MISO_1") (pintype "passive"))
    )
    (net (code "102") (name "unconnected-(ICSP-MOSI-Pad4)") (class "Default")
      (node (ref "ICSP") (pin "4") (pinfunction "MOSI_4") (pintype "passive"))
    )
    (net (code "103") (name "unconnected-(ICSP-RESET-Pad5)") (class "Default")
      (node (ref "ICSP") (pin "5") (pinfunction "RESET_5") (pintype "passive"))
    )
    (net (code "104") (name "unconnected-(ICSP-SCK-Pad3)") (class "Default")
      (node (ref "ICSP") (pin "3") (pinfunction "SCK_3") (pintype "passive"))
    )
    (net (code "105") (name "unconnected-(POWER-3V3-Pad5)") (class "Default")
      (node (ref "POWER") (pin "5") (pinfunction "3V3_5") (pintype "power_in"))
    )
    (net (code "106") (name "unconnected-(POWER-RESET-Pad6)") (class "Default")
      (node (ref "POWER") (pin "6") (pinfunction "RESET_6") (pintype "passive"))
    )
    (net (code "107") (name "unconnected-(PWM_H-AREF-Pad8)") (class "Default")
      (node (ref "PWM_H") (pin "8") (pinfunction "AREF_8") (pintype "passive"))
    )
    (net (code "108") (name "unconnected-(PWM_H-PWM8-Pad1)") (class "Default")
      (node (ref "PWM_H") (pin "1") (pinfunction "PWM8_1") (pintype "passive"))
    )
    (net (code "109") (name "unconnected-(PWM_H-PWM9-Pad2)") (class "Default")
      (node (ref "PWM_H") (pin "2") (pinfunction "PWM9_2") (pintype "passive"))
    )
    (net (code "110") (name "unconnected-(PWM_H-PWM10-Pad3)") (class "Default")
      (node (ref "PWM_H") (pin "3") (pinfunction "PWM10_3") (pintype "passive"))
    )
    (net (code "111") (name "unconnected-(PWM_H-PWM11-Pad4)") (class "Default")
      (node (ref "PWM_H") (pin "4") (pinfunction "PWM11_4") (pintype "passive"))
    )
    (net (code "112") (name "unconnected-(PWM_H-PWM12-Pad5)") (class "Default")
      (node (ref "PWM_H") (pin "5") (pinfunction "PWM12_5") (pintype "passive"))
    )
    (net (code "113") (name "unconnected-(PWM_H-PWM13-Pad6)") (class "Default")
      (node (ref "PWM_H") (pin "6") (pinfunction "PWM13_6") (pintype "passive"))
    )
    (net (code "114") (name "unconnected-(PWM_L-RX0-Pad1)") (class "Default")
      (node (ref "PWM_L") (pin "1") (pinfunction "RX0_1") (pintype "passive"))
    )
    (net (code "115") (name "unconnected-(PWM_L-TX0-Pad2)") (class "Default")
      (node (ref "PWM_L") (pin "2") (pinfunction "TX0_2") (pintype "passive"))
    )
    (net (code "116") (name "unconnected-(U1-QH#-Pad9)") (class "Default")
      (node (ref "U1") (pin "9") (pinfunction "QH#_9") (pintype "passive"))
    )
    (net (code "117") (name "unconnected-(U2-QH#-Pad9)") (class "Default")
      (node (ref "U2") (pin "9") (pinfunction "QH#_9") (pintype "passive"))
    )
    (net (code "118") (name "unconnected-(U3-QE-Pad4)") (class "Default")
      (node (ref "U3") (pin "4") (pinfunction "QE_4") (pintype "passive"))
    )
    (net (code "119") (name "unconnected-(U3-QF-Pad5)") (class "Default")
      (node (ref "U3") (pin "5") (pinfunction "QF_5") (pintype "passive"))
    )
    (net (code "120") (name "unconnected-(U3-QG-Pad6)") (class "Default")
      (node (ref "U3") (pin "6") (pinfunction "QG_6") (pintype "passive"))
    )
    (net (code "121") (name "unconnected-(U3-QH#-Pad9)") (class "Default")
      (node (ref "U3") (pin "9") (pinfunction "QH#_9") (pintype "passive"))
    )
    (net (code "122") (name "unconnected-(U3-QH-Pad7)") (class "Default")
      (node (ref "U3") (pin "7") (pinfunction "QH_7") (pintype "passive"))
    )
  )
)
